# untitled.net
KiCad netlist of a schematic drawn in EAGLE
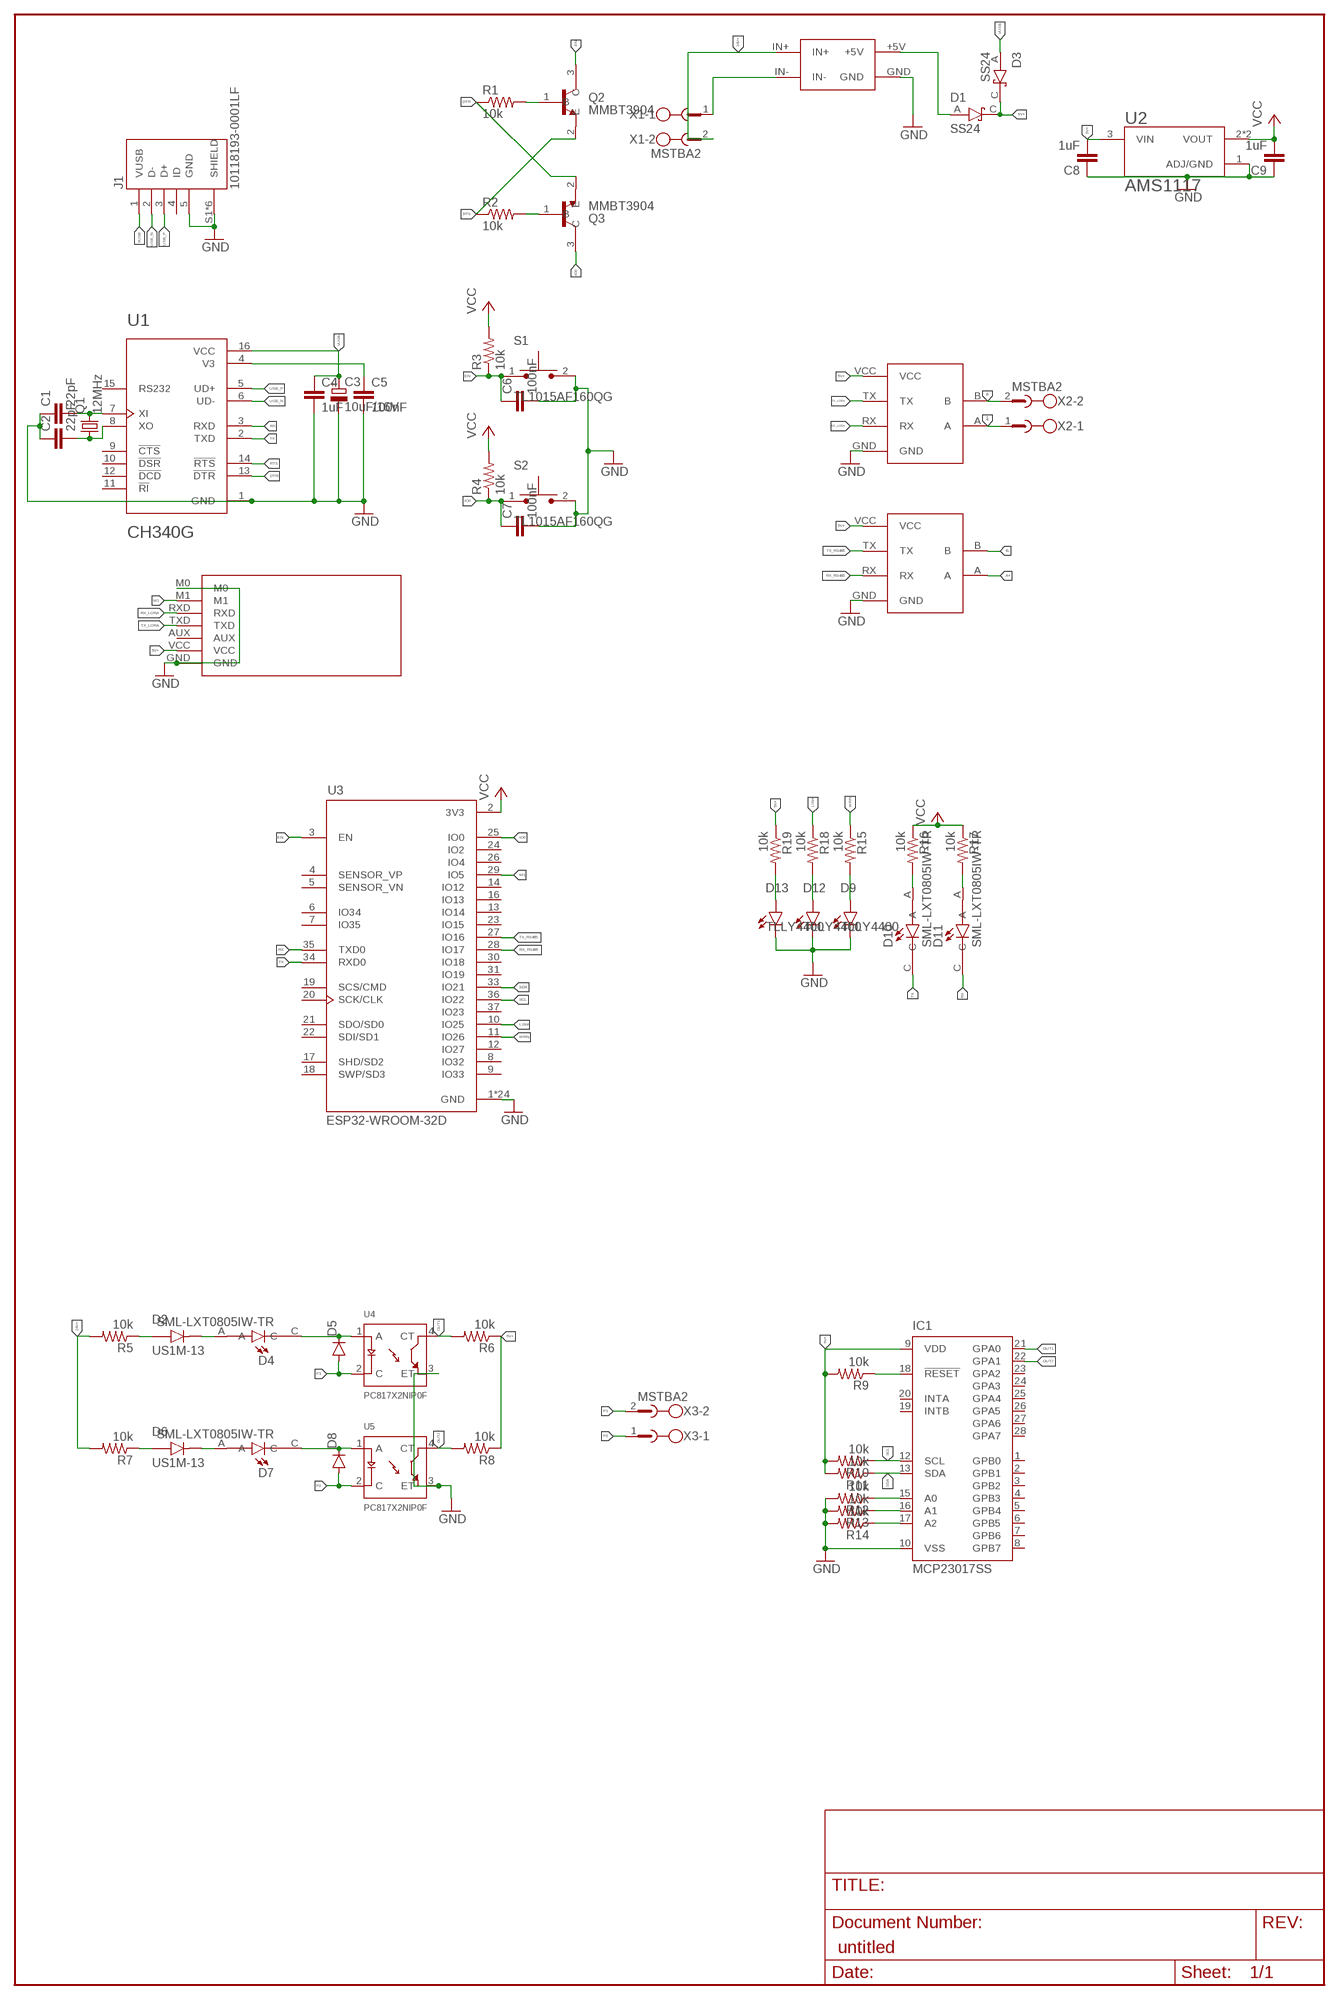
[diagram p0: schematic, sheet 1]

(export (version "E")
  (design (tool "Eeschema 10.0.6"))
  (components
    (comp (ref "C1")
      (value "22pF")
      (footprint "eagle-import:C0805K")
      (libsource (lib "eagle-import") (part "C-EUC0805K"))
    )
    (comp (ref "C2")
      (value "22pF")
      (footprint "eagle-import:C0805K")
      (libsource (lib "eagle-import") (part "C-EUC0805K"))
    )
    (comp (ref "C3")
      (value "10uF/16V")
      (footprint "eagle-import:153CLV-0505")
      (libsource (lib "eagle-import") (part "CPOL-EU153CLV-0505"))
    )
    (comp (ref "C4")
      (value "1uF")
      (footprint "eagle-import:C0805K")
      (libsource (lib "eagle-import") (part "C-EUC0805K"))
    )
    (comp (ref "C5")
      (value "100nF")
      (footprint "eagle-import:C0805K")
      (libsource (lib "eagle-import") (part "C-EUC0805K"))
    )
    (comp (ref "C6")
      (value "100nF")
      (footprint "eagle-import:C0805K")
      (libsource (lib "eagle-import") (part "C-EUC0805K"))
    )
    (comp (ref "C7")
      (value "100nF")
      (footprint "eagle-import:C0805K")
      (libsource (lib "eagle-import") (part "C-EUC0805K"))
    )
    (comp (ref "C8")
      (value "1uF")
      (footprint "eagle-import:C0805K")
      (libsource (lib "eagle-import") (part "C-EUC0805K"))
    )
    (comp (ref "C9")
      (value "1uF")
      (footprint "eagle-import:C0805K")
      (libsource (lib "eagle-import") (part "C-EUC0805K"))
    )
    (comp (ref "D1")
      (value "SS24")
      (footprint "eagle-import:DIOM5336X265N")
      (fields (field (name "MF") "ON Semiconductor"))
      (libsource (lib "eagle-import") (part "SS24"))
    )
    (comp (ref "D2")
      (value "US1M-13")
      (footprint "eagle-import:DIOM5226X240N")
      (fields (field (name "MF") "Diodes Incorporated"))
      (libsource (lib "eagle-import") (part "US1M-13"))
    )
    (comp (ref "D3")
      (value "SS24")
      (footprint "eagle-import:DIOM5336X265N")
      (fields (field (name "MF") "ON Semiconductor"))
      (libsource (lib "eagle-import") (part "SS24"))
    )
    (comp (ref "D4")
      (value "SML-LXT0805IW-TR")
      (footprint "eagle-import:LEDC2012X120N")
      (fields (field (name "MF") "Lumex Opto/Components"))
      (libsource (lib "eagle-import") (part "SML-LXT0805IW-TR"))
    )
    (comp (ref "D5")
      (value "DIODE-SOD123")
      (footprint "eagle-import:SOD123")
      (libsource (lib "eagle-import") (part "DIODE-SOD123"))
    )
    (comp (ref "D6")
      (value "US1M-13")
      (footprint "eagle-import:DIOM5226X240N")
      (fields (field (name "MF") "Diodes Incorporated"))
      (libsource (lib "eagle-import") (part "US1M-13"))
    )
    (comp (ref "D7")
      (value "SML-LXT0805IW-TR")
      (footprint "eagle-import:LEDC2012X120N")
      (fields (field (name "MF") "Lumex Opto/Components"))
      (libsource (lib "eagle-import") (part "SML-LXT0805IW-TR"))
    )
    (comp (ref "D8")
      (value "DIODE-SOD123")
      (footprint "eagle-import:SOD123")
      (libsource (lib "eagle-import") (part "DIODE-SOD123"))
    )
    (comp (ref "D9")
      (value "TLLY4400")
      (footprint "eagle-import:LED3MM")
      (fields (field (name "MF") "VISHAY SEMICONDUCTOR"))
      (libsource (lib "eagle-import") (part "TLLY4400"))
    )
    (comp (ref "D10")
      (value "SML-LXT0805IW-TR")
      (footprint "eagle-import:LEDC2012X120N")
      (fields (field (name "MF") "Lumex Opto/Components"))
      (libsource (lib "eagle-import") (part "SML-LXT0805IW-TR"))
    )
    (comp (ref "D11")
      (value "SML-LXT0805IW-TR")
      (footprint "eagle-import:LEDC2012X120N")
      (fields (field (name "MF") "Lumex Opto/Components"))
      (libsource (lib "eagle-import") (part "SML-LXT0805IW-TR"))
    )
    (comp (ref "D12")
      (value "TLLY4400")
      (footprint "eagle-import:LED3MM")
      (fields (field (name "MF") "VISHAY SEMICONDUCTOR"))
      (libsource (lib "eagle-import") (part "TLLY4400"))
    )
    (comp (ref "D13")
      (value "TLLY4400")
      (footprint "eagle-import:LED3MM")
      (fields (field (name "MF") "VISHAY SEMICONDUCTOR"))
      (libsource (lib "eagle-import") (part "TLLY4400"))
    )
    (comp (ref "EBYTEE220-900T22D1")
      (value "EBYTEE220-900T22D")
      (footprint "eagle-import:EBYTEE220-900T22D")
      (libsource (lib "eagle-import") (part "EBYTEE220-900T22D"))
    )
    (comp (ref "IC1")
      (value "MCP23017SS")
      (footprint "eagle-import:SSOP28")
      (fields (field (name "MF") "MICROCHIP") (field (name "MPN") "MCP23017-E/SS"))
      (libsource (lib "eagle-import") (part "MCP23017SS"))
    )
    (comp (ref "J1")
      (value "10118193-0001LF")
      (footprint "eagle-import:FCI_10118193-0001LF")
      (fields (field (name "MF") "FCI"))
      (libsource (lib "eagle-import") (part "10118193-0001LF"))
    )
    (comp (ref "Q1")
      (value "12MHz")
      (footprint "eagle-import:SM49")
      (libsource (lib "eagle-import") (part "CRYSTALSM49"))
    )
    (comp (ref "Q2")
      (value "MMBT3904")
      (footprint "eagle-import:SOT95P240X120-3N")
      (fields (field (name "MF") "ON Semiconductor"))
      (libsource (lib "eagle-import") (part "MMBT3904"))
    )
    (comp (ref "Q3")
      (value "MMBT3904")
      (footprint "eagle-import:SOT95P240X120-3N")
      (fields (field (name "MF") "ON Semiconductor"))
      (libsource (lib "eagle-import") (part "MMBT3904"))
    )
    (comp (ref "R1")
      (value "10k")
      (footprint "eagle-import:M0805")
      (libsource (lib "eagle-import") (part "rcl_334_R-US_M0805"))
    )
    (comp (ref "R2")
      (value "10k")
      (footprint "eagle-import:M0805")
      (libsource (lib "eagle-import") (part "rcl_334_R-US_M0805"))
    )
    (comp (ref "R3")
      (value "10k")
      (footprint "eagle-import:M0805")
      (libsource (lib "eagle-import") (part "rcl_334_R-US_M0805"))
    )
    (comp (ref "R4")
      (value "10k")
      (footprint "eagle-import:M0805")
      (libsource (lib "eagle-import") (part "rcl_334_R-US_M0805"))
    )
    (comp (ref "R5")
      (value "10k")
      (footprint "eagle-import:0207_12")
      (libsource (lib "eagle-import") (part "R-US_0207/12"))
    )
    (comp (ref "R6")
      (value "10k")
      (footprint "eagle-import:M0805")
      (libsource (lib "eagle-import") (part "rcl_334_R-US_M0805"))
    )
    (comp (ref "R7")
      (value "10k")
      (footprint "eagle-import:0207_12")
      (libsource (lib "eagle-import") (part "R-US_0207/12"))
    )
    (comp (ref "R8")
      (value "10k")
      (footprint "eagle-import:M0805")
      (libsource (lib "eagle-import") (part "rcl_334_R-US_M0805"))
    )
    (comp (ref "R9")
      (value "10k")
      (footprint "eagle-import:M0805")
      (libsource (lib "eagle-import") (part "rcl_334_R-US_M0805"))
    )
    (comp (ref "R10")
      (value "10k")
      (footprint "eagle-import:M0805")
      (libsource (lib "eagle-import") (part "rcl_334_R-US_M0805"))
    )
    (comp (ref "R11")
      (value "10k")
      (footprint "eagle-import:M0805")
      (libsource (lib "eagle-import") (part "rcl_334_R-US_M0805"))
    )
    (comp (ref "R12")
      (value "10k")
      (footprint "eagle-import:M0805")
      (libsource (lib "eagle-import") (part "rcl_334_R-US_M0805"))
    )
    (comp (ref "R13")
      (value "10k")
      (footprint "eagle-import:M0805")
      (libsource (lib "eagle-import") (part "rcl_334_R-US_M0805"))
    )
    (comp (ref "R14")
      (value "10k")
      (footprint "eagle-import:M0805")
      (libsource (lib "eagle-import") (part "rcl_334_R-US_M0805"))
    )
    (comp (ref "R15")
      (value "10k")
      (footprint "eagle-import:M0805")
      (libsource (lib "eagle-import") (part "rcl_334_R-US_M0805"))
    )
    (comp (ref "R16")
      (value "10k")
      (footprint "eagle-import:M0805")
      (libsource (lib "eagle-import") (part "rcl_334_R-US_M0805"))
    )
    (comp (ref "R17")
      (value "10k")
      (footprint "eagle-import:M0805")
      (libsource (lib "eagle-import") (part "rcl_334_R-US_M0805"))
    )
    (comp (ref "R18")
      (value "10k")
      (footprint "eagle-import:M0805")
      (libsource (lib "eagle-import") (part "rcl_334_R-US_M0805"))
    )
    (comp (ref "R19")
      (value "10k")
      (footprint "eagle-import:M0805")
      (libsource (lib "eagle-import") (part "rcl_334_R-US_M0805"))
    )
    (comp (ref "S1")
      (value "TL1015AF160QG")
      (footprint "eagle-import:SW_TL1015AF160QG")
      (fields (field (name "MF") "E-Switch"))
      (libsource (lib "eagle-import") (part "TL1015AF160QG"))
    )
    (comp (ref "S2")
      (value "TL1015AF160QG")
      (footprint "eagle-import:SW_TL1015AF160QG")
      (fields (field (name "MF") "E-Switch"))
      (libsource (lib "eagle-import") (part "TL1015AF160QG"))
    )
    (comp (ref "SUPER-STEPDOWN1")
      (value "SUPER-STEPDOWN")
      (footprint "eagle-import:SUPER-STEPDOWN")
      (libsource (lib "eagle-import") (part "SUPER-STEPDOWN"))
    )
    (comp (ref "TTL-RS1")
      (value "TTL-RS485")
      (footprint "eagle-import:TTL-RS485")
      (libsource (lib "eagle-import") (part "TTL-RS485"))
    )
    (comp (ref "TTL-RS2")
      (value "TTL-RS485")
      (footprint "eagle-import:TTL-RS485")
      (libsource (lib "eagle-import") (part "TTL-RS485"))
    )
    (comp (ref "U1")
      (value "CH340G")
      (footprint "eagle-import:SOIC127P600X180-16N")
      (fields (field (name "MF") "WCH") (field (name "MP") "Ch340G"))
      (libsource (lib "eagle-import") (part "CH340G"))
    )
    (comp (ref "U2")
      (value "AMS1117")
      (footprint "eagle-import:SOT229P700X180-4N")
      (fields (field (name "MF") "Advanced Monolithic Systems"))
      (libsource (lib "eagle-import") (part "AMS1117"))
    )
    (comp (ref "U3")
      (value "ESP32-WROOM-32D")
      (footprint "eagle-import:MODULE_ESP32-WROOM-32D")
      (fields (field (name "MF") "Espressif Systems"))
      (libsource (lib "eagle-import") (part "ESP32-WROOM-32D"))
    )
    (comp (ref "U4")
      (value "PC817X2NIP0F")
      (footprint "eagle-import:SOT254P975X400-4N")
      (fields (field (name "MF") "Sharp Microelectronics"))
      (libsource (lib "eagle-import") (part "PC817X2NIP0F"))
    )
    (comp (ref "U5")
      (value "PC817X2NIP0F")
      (footprint "eagle-import:SOT254P975X400-4N")
      (fields (field (name "MF") "Sharp Microelectronics"))
      (libsource (lib "eagle-import") (part "PC817X2NIP0F"))
    )
    (comp (ref "X1")
      (value "MSTBA2")
      (footprint "eagle-import:MSTBA2")
      (fields (field (name "MF") "FARNELL") (field (name "MPN") "1757242"))
      (libsource (lib "eagle-import") (part "MSTBA2"))
    )
    (comp (ref "X2")
      (value "MSTBA2")
      (footprint "eagle-import:MSTBA2")
      (fields (field (name "MF") "FARNELL") (field (name "MPN") "1757242"))
      (libsource (lib "eagle-import") (part "MSTBA2"))
    )
    (comp (ref "X3")
      (value "MSTBA2")
      (footprint "eagle-import:MSTBA2")
      (fields (field (name "MF") "FARNELL") (field (name "MPN") "1757242"))
      (libsource (lib "eagle-import") (part "MSTBA2"))
    )
  )
  (nets
    (net (code "1") (name "5V+") (class "Default")
      (node (ref "C8") (pin "2") (pinfunction "2_2") (pintype "passive"))
      (node (ref "D1") (pin "C") (pinfunction "K_C") (pintype "passive"))
      (node (ref "D3") (pin "C") (pinfunction "K_C") (pintype "passive"))
      (node (ref "EBYTEE220-900T22D1") (pin "VCC") (pinfunction "VCC_VCC") (pintype "bidirectional"))
      (node (ref "IC1") (pin "9") (pinfunction "VDD_9") (pintype "power_in"))
      (node (ref "R10") (pin "2") (pinfunction "2_2") (pintype "passive"))
      (node (ref "R11") (pin "2") (pinfunction "2_2") (pintype "passive"))
      (node (ref "R19") (pin "1") (pinfunction "1_1") (pintype "passive"))
      (node (ref "R6") (pin "1") (pinfunction "1_1") (pintype "passive"))
      (node (ref "R8") (pin "1") (pinfunction "1_1") (pintype "passive"))
      (node (ref "R9") (pin "2") (pinfunction "2_2") (pintype "passive"))
      (node (ref "TTL-RS1") (pin "VCC") (pinfunction "VCC_VCC") (pintype "bidirectional"))
      (node (ref "TTL-RS2") (pin "VCC") (pinfunction "VCC_VCC") (pintype "bidirectional"))
      (node (ref "U2") (pin "3") (pinfunction "VIN_3") (pintype "input"))
    )
    (net (code "2") (name "24V+") (class "Default")
      (node (ref "R5") (pin "2") (pinfunction "2_2") (pintype "passive"))
      (node (ref "R7") (pin "2") (pinfunction "2_2") (pintype "passive"))
      (node (ref "SUPER-STEPDOWN1") (pin "IN+") (pinfunction "IN+_IN+") (pintype "bidirectional"))
      (node (ref "X1") (pin "2") (pinfunction "1_2") (pintype "passive"))
    )
    (net (code "3") (name "A+") (class "Default")
      (node (ref "TTL-RS1") (pin "A") (pinfunction "A_A") (pintype "bidirectional"))
      (node (ref "TTL-RS2") (pin "A") (pinfunction "A_A") (pintype "bidirectional"))
      (node (ref "X2") (pin "1") (pinfunction "1_1") (pintype "passive"))
    )
    (net (code "4") (name "B-") (class "Default")
      (node (ref "TTL-RS1") (pin "B") (pinfunction "B_B") (pintype "bidirectional"))
      (node (ref "TTL-RS2") (pin "B") (pinfunction "B_B") (pintype "bidirectional"))
      (node (ref "X2") (pin "2") (pinfunction "1_2") (pintype "passive"))
    )
    (net (code "5") (name "DTR") (class "Default")
      (node (ref "Q3") (pin "2") (pinfunction "E_2") (pintype "passive"))
      (node (ref "R1") (pin "1") (pinfunction "1_1") (pintype "passive"))
      (node (ref "U1") (pin "13") (pinfunction "~{DTR}_13") (pintype "output"))
    )
    (net (code "6") (name "EN") (class "Default")
      (node (ref "C6") (pin "1") (pinfunction "1_1") (pintype "passive"))
      (node (ref "Q2") (pin "3") (pinfunction "C_3") (pintype "passive"))
      (node (ref "R3") (pin "1") (pinfunction "1_1") (pintype "passive"))
      (node (ref "S1") (pin "1") (pinfunction "1_1") (pintype "passive"))
      (node (ref "U3") (pin "3") (pinfunction "EN_3") (pintype "input"))
    )
    (net (code "7") (name "GND") (class "Default")
      (node (ref "C1") (pin "1") (pinfunction "1_1") (pintype "passive"))
      (node (ref "C2") (pin "1") (pinfunction "1_1") (pintype "passive"))
      (node (ref "C3") (pin "-") (pinfunction "-_-") (pintype "passive"))
      (node (ref "C4") (pin "2") (pinfunction "2_2") (pintype "passive"))
      (node (ref "C5") (pin "2") (pinfunction "2_2") (pintype "passive"))
      (node (ref "C6") (pin "2") (pinfunction "2_2") (pintype "passive"))
      (node (ref "C7") (pin "2") (pinfunction "2_2") (pintype "passive"))
      (node (ref "C8") (pin "1") (pinfunction "1_1") (pintype "passive"))
      (node (ref "C9") (pin "1") (pinfunction "1_1") (pintype "passive"))
      (node (ref "D12") (pin "K") (pinfunction "C_K") (pintype "passive"))
      (node (ref "D13") (pin "K") (pinfunction "C_K") (pintype "passive"))
      (node (ref "D9") (pin "K") (pinfunction "C_K") (pintype "passive"))
      (node (ref "EBYTEE220-900T22D1") (pin "GND") (pinfunction "GND_GND") (pintype "bidirectional"))
      (node (ref "EBYTEE220-900T22D1") (pin "M0") (pinfunction "M0_M0") (pintype "bidirectional"))
      (node (ref "IC1") (pin "10") (pinfunction "VSS_10") (pintype "power_in"))
      (node (ref "J1") (pin "5") (pinfunction "GND_5") (pintype "passive"))
      (node (ref "J1") (pin "S1") (pinfunction "SHIELD_S1") (pintype "passive"))
      (node (ref "J1") (pin "S2") (pinfunction "SHIELD_S2") (pintype "passive"))
      (node (ref "J1") (pin "S3") (pinfunction "SHIELD_S3") (pintype "passive"))
      (node (ref "J1") (pin "S4") (pinfunction "SHIELD_S4") (pintype "passive"))
      (node (ref "J1") (pin "S5") (pinfunction "SHIELD_S5") (pintype "passive"))
      (node (ref "J1") (pin "S6") (pinfunction "SHIELD_S6") (pintype "passive"))
      (node (ref "R12") (pin "2") (pinfunction "2_2") (pintype "passive"))
      (node (ref "R13") (pin "2") (pinfunction "2_2") (pintype "passive"))
      (node (ref "R14") (pin "2") (pinfunction "2_2") (pintype "passive"))
      (node (ref "S1") (pin "2") (pinfunction "2_2") (pintype "passive"))
      (node (ref "S2") (pin "2") (pinfunction "2_2") (pintype "passive"))
      (node (ref "SUPER-STEPDOWN1") (pin "GND") (pinfunction "GND_GND") (pintype "bidirectional"))
      (node (ref "TTL-RS1") (pin "GND") (pinfunction "GND_GND") (pintype "bidirectional"))
      (node (ref "TTL-RS2") (pin "GND") (pinfunction "GND_GND") (pintype "bidirectional"))
      (node (ref "U1") (pin "1") (pinfunction "GND_1") (pintype "power_in"))
      (node (ref "U2") (pin "1") (pinfunction "ADJ/GND_1") (pintype "power_in"))
      (node (ref "U3") (pin "1") (pinfunction "GND_1") (pintype "power_in"))
      (node (ref "U3") (pin "15") (pinfunction "GND_15") (pintype "power_in"))
      (node (ref "U3") (pin "38") (pinfunction "GND_38") (pintype "power_in"))
      (node (ref "U3") (pin "39_1") (pinfunction "GND_39_1") (pintype "power_in"))
      (node (ref "U3") (pin "39_10") (pinfunction "GND_39_10") (pintype "power_in"))
      (node (ref "U3") (pin "39_11") (pinfunction "GND_39_11") (pintype "power_in"))
      (node (ref "U3") (pin "39_12") (pinfunction "GND_39_12") (pintype "power_in"))
      (node (ref "U3") (pin "39_13") (pinfunction "GND_39_13") (pintype "power_in"))
      (node (ref "U3") (pin "39_14") (pinfunction "GND_39_14") (pintype "power_in"))
      (node (ref "U3") (pin "39_15") (pinfunction "GND_39_15") (pintype "power_in"))
      (node (ref "U3") (pin "39_16") (pinfunction "GND_39_16") (pintype "power_in"))
      (node (ref "U3") (pin "39_17") (pinfunction "GND_39_17") (pintype "power_in"))
      (node (ref "U3") (pin "39_18") (pinfunction "GND_39_18") (pintype "power_in"))
      (node (ref "U3") (pin "39_19") (pinfunction "GND_39_19") (pintype "power_in"))
      (node (ref "U3") (pin "39_2") (pinfunction "GND_39_2") (pintype "power_in"))
      (node (ref "U3") (pin "39_20") (pinfunction "GND_39_20") (pintype "power_in"))
      (node (ref "U3") (pin "39_21") (pinfunction "GND_39_21") (pintype "power_in"))
      (node (ref "U3") (pin "39_3") (pinfunction "GND_39_3") (pintype "power_in"))
      (node (ref "U3") (pin "39_4") (pinfunction "GND_39_4") (pintype "power_in"))
      (node (ref "U3") (pin "39_5") (pinfunction "GND_39_5") (pintype "power_in"))
      (node (ref "U3") (pin "39_6") (pinfunction "GND_39_6") (pintype "power_in"))
      (node (ref "U3") (pin "39_7") (pinfunction "GND_39_7") (pintype "power_in"))
      (node (ref "U3") (pin "39_8") (pinfunction "GND_39_8") (pintype "power_in"))
      (node (ref "U3") (pin "39_9") (pinfunction "GND_39_9") (pintype "power_in"))
      (node (ref "U4") (pin "3") (pinfunction "ET_3") (pintype "passive"))
      (node (ref "U5") (pin "3") (pinfunction "ET_3") (pintype "passive"))
    )
    (net (code "8") (name "IO0") (class "Default")
      (node (ref "C7") (pin "1") (pinfunction "1_1") (pintype "passive"))
      (node (ref "Q3") (pin "3") (pinfunction "C_3") (pintype "passive"))
      (node (ref "R4") (pin "1") (pinfunction "1_1") (pintype "passive"))
      (node (ref "S2") (pin "1") (pinfunction "1_1") (pintype "passive"))
      (node (ref "U3") (pin "25") (pinfunction "IO0_25") (pintype "bidirectional"))
    )
    (net (code "9") (name "LINK") (class "Default")
      (node (ref "R18") (pin "1") (pinfunction "1_1") (pintype "passive"))
      (node (ref "U3") (pin "10") (pinfunction "IO25_10") (pintype "bidirectional"))
    )
    (net (code "10") (name "M1") (class "Default")
      (node (ref "EBYTEE220-900T22D1") (pin "M1") (pinfunction "M1_M1") (pintype "bidirectional"))
      (node (ref "U3") (pin "29") (pinfunction "IO5_29") (pintype "bidirectional"))
    )
    (net (code "11") (name "Net-(D1-PadA)") (class "Default")
      (node (ref "D1") (pin "A") (pinfunction "A_A") (pintype "passive"))
      (node (ref "SUPER-STEPDOWN1") (pin "+5V") (pinfunction "+5V_+5V") (pintype "bidirectional"))
    )
    (net (code "12") (name "Net-(D2-K)") (class "Default")
      (node (ref "D2") (pin "C") (pinfunction "K_C") (pintype "passive"))
      (node (ref "D4") (pin "A") (pinfunction "A_A") (pintype "passive"))
    )
    (net (code "13") (name "Net-(D2-PadA)") (class "Default")
      (node (ref "D2") (pin "A") (pinfunction "A_A") (pintype "passive"))
      (node (ref "R5") (pin "1") (pinfunction "1_1") (pintype "passive"))
    )
    (net (code "14") (name "Net-(D6-K)") (class "Default")
      (node (ref "D6") (pin "C") (pinfunction "K_C") (pintype "passive"))
      (node (ref "D7") (pin "A") (pinfunction "A_A") (pintype "passive"))
    )
    (net (code "15") (name "Net-(D6-PadA)") (class "Default")
      (node (ref "D6") (pin "A") (pinfunction "A_A") (pintype "passive"))
      (node (ref "R7") (pin "1") (pinfunction "1_1") (pintype "passive"))
    )
    (net (code "16") (name "Net-(D9-PadA)") (class "Default")
      (node (ref "D9") (pin "A") (pinfunction "A_A") (pintype "passive"))
      (node (ref "R15") (pin "2") (pinfunction "2_2") (pintype "passive"))
    )
    (net (code "17") (name "Net-(D10-PadA)") (class "Default")
      (node (ref "D10") (pin "A") (pinfunction "A_A") (pintype "passive"))
      (node (ref "R16") (pin "2") (pinfunction "2_2") (pintype "passive"))
    )
    (net (code "18") (name "Net-(D11-PadA)") (class "Default")
      (node (ref "D11") (pin "A") (pinfunction "A_A") (pintype "passive"))
      (node (ref "R17") (pin "2") (pinfunction "2_2") (pintype "passive"))
    )
    (net (code "19") (name "Net-(D12-PadA)") (class "Default")
      (node (ref "D12") (pin "A") (pinfunction "A_A") (pintype "passive"))
      (node (ref "R18") (pin "2") (pinfunction "2_2") (pintype "passive"))
    )
    (net (code "20") (name "Net-(D13-PadA)") (class "Default")
      (node (ref "D13") (pin "A") (pinfunction "A_A") (pintype "passive"))
      (node (ref "R19") (pin "2") (pinfunction "2_2") (pintype "passive"))
    )
    (net (code "21") (name "Net-(IC1-A0)") (class "Default")
      (node (ref "IC1") (pin "15") (pinfunction "A0_15") (pintype "input"))
      (node (ref "R12") (pin "1") (pinfunction "1_1") (pintype "passive"))
    )
    (net (code "22") (name "Net-(IC1-A1)") (class "Default")
      (node (ref "IC1") (pin "16") (pinfunction "A1_16") (pintype "input"))
      (node (ref "R13") (pin "1") (pinfunction "1_1") (pintype "passive"))
    )
    (net (code "23") (name "Net-(IC1-A2)") (class "Default")
      (node (ref "IC1") (pin "17") (pinfunction "A2_17") (pintype "input"))
      (node (ref "R14") (pin "1") (pinfunction "1_1") (pintype "passive"))
    )
    (net (code "24") (name "Net-(IC1-~{RESET})") (class "Default")
      (node (ref "IC1") (pin "18") (pinfunction "~{RESET}_18") (pintype "input"))
      (node (ref "R9") (pin "1") (pinfunction "1_1") (pintype "passive"))
    )
    (net (code "25") (name "Net-(Q2-B)") (class "Default")
      (node (ref "Q2") (pin "1") (pinfunction "B_1") (pintype "passive"))
      (node (ref "R1") (pin "2") (pinfunction "2_2") (pintype "passive"))
    )
    (net (code "26") (name "Net-(Q3-B)") (class "Default")
      (node (ref "Q3") (pin "1") (pinfunction "B_1") (pintype "passive"))
      (node (ref "R2") (pin "2") (pinfunction "2_2") (pintype "passive"))
    )
    (net (code "27") (name "Net-(SUPER-STEPDOWN1-PadIN-)") (class "Default")
      (node (ref "SUPER-STEPDOWN1") (pin "IN-") (pinfunction "IN-_IN-") (pintype "bidirectional"))
      (node (ref "X1") (pin "1") (pinfunction "1_1") (pintype "passive"))
    )
    (net (code "28") (name "Net-(U1-V3)") (class "Default")
      (node (ref "C5") (pin "1") (pinfunction "1_1") (pintype "passive"))
      (node (ref "U1") (pin "4") (pinfunction "V3_4") (pintype "power_in"))
    )
    (net (code "29") (name "Net-(U1-XI)") (class "Default")
      (node (ref "C1") (pin "2") (pinfunction "2_2") (pintype "passive"))
      (node (ref "Q1") (pin "2") (pinfunction "2_2") (pintype "passive"))
      (node (ref "U1") (pin "7") (pinfunction "XI_7") (pintype "input"))
    )
    (net (code "30") (name "Net-(U1-XO)") (class "Default")
      (node (ref "C2") (pin "2") (pinfunction "2_2") (pintype "passive"))
      (node (ref "Q1") (pin "1") (pinfunction "1_1") (pintype "passive"))
      (node (ref "U1") (pin "8") (pinfunction "XO_8") (pintype "output"))
    )
    (net (code "31") (name "Net-(U4-A)") (class "Default")
      (node (ref "D4") (pin "C") (pinfunction "C_C") (pintype "passive"))
      (node (ref "D5") (pin "C") (pinfunction "C_C") (pintype "passive"))
      (node (ref "U4") (pin "1") (pinfunction "A_1") (pintype "passive"))
    )
    (net (code "32") (name "Net-(U5-A)") (class "Default")
      (node (ref "D7") (pin "C") (pinfunction "C_C") (pintype "passive"))
      (node (ref "D8") (pin "C") (pinfunction "C_C") (pintype "passive"))
      (node (ref "U5") (pin "1") (pinfunction "A_1") (pintype "passive"))
    )
    (net (code "33") (name "OUT1") (class "Default")
      (node (ref "IC1") (pin "21") (pinfunction "GPA0_21") (pintype "bidirectional"))
      (node (ref "R6") (pin "2") (pinfunction "2_2") (pintype "passive"))
      (node (ref "U4") (pin "4") (pinfunction "CT_4") (pintype "passive"))
    )
    (net (code "34") (name "OUT2") (class "Default")
      (node (ref "IC1") (pin "22") (pinfunction "GPA1_22") (pintype "bidirectional"))
      (node (ref "R8") (pin "2") (pinfunction "2_2") (pintype "passive"))
      (node (ref "U5") (pin "4") (pinfunction "CT_4") (pintype "passive"))
    )
    (net (code "35") (name "P1") (class "Default")
      (node (ref "D5") (pin "A") (pinfunction "A_A") (pintype "passive"))
      (node (ref "U4") (pin "2") (pinfunction "C_2") (pintype "passive"))
      (node (ref "X3") (pin "2") (pinfunction "1_2") (pintype "passive"))
    )
    (net (code "36") (name "P2") (class "Default")
      (node (ref "D8") (pin "A") (pinfunction "A_A") (pintype "passive"))
      (node (ref "U5") (pin "2") (pinfunction "C_2") (pintype "passive"))
      (node (ref "X3") (pin "1") (pinfunction "1_1") (pintype "passive"))
    )
    (net (code "37") (name "RTS") (class "Default")
      (node (ref "Q2") (pin "2") (pinfunction "E_2") (pintype "passive"))
      (node (ref "R2") (pin "1") (pinfunction "1_1") (pintype "passive"))
      (node (ref "U1") (pin "14") (pinfunction "~{RTS}_14") (pintype "output"))
    )
    (net (code "38") (name "RX") (class "Default")
      (node (ref "D11") (pin "C") (pinfunction "C_C") (pintype "passive"))
      (node (ref "U1") (pin "3") (pinfunction "RXD_3") (pintype "input"))
      (node (ref "U3") (pin "35") (pinfunction "TXD0_35") (pintype "bidirectional"))
    )
    (net (code "39") (name "RX_LORA") (class "Default")
      (node (ref "EBYTEE220-900T22D1") (pin "RXD") (pinfunction "RXD_RXD") (pintype "bidirectional"))
      (node (ref "TTL-RS1") (pin "RX") (pinfunction "RX_RX") (pintype "bidirectional"))
    )
    (net (code "40") (name "RX_RS485") (class "Default")
      (node (ref "TTL-RS2") (pin "RX") (pinfunction "RX_RX") (pintype "bidirectional"))
      (node (ref "U3") (pin "28") (pinfunction "IO17_28") (pintype "bidirectional"))
    )
    (net (code "41") (name "SCL") (class "Default")
      (node (ref "IC1") (pin "12") (pinfunction "SCL_12") (pintype "input"))
      (node (ref "R10") (pin "1") (pinfunction "1_1") (pintype "passive"))
      (node (ref "U3") (pin "36") (pinfunction "IO22_36") (pintype "bidirectional"))
    )
    (net (code "42") (name "SDA") (class "Default")
      (node (ref "IC1") (pin "13") (pinfunction "SDA_13") (pintype "bidirectional"))
      (node (ref "R11") (pin "1") (pinfunction "1_1") (pintype "passive"))
      (node (ref "U3") (pin "33") (pinfunction "IO21_33") (pintype "bidirectional"))
    )
    (net (code "43") (name "TX") (class "Default")
      (node (ref "D10") (pin "C") (pinfunction "C_C") (pintype "passive"))
      (node (ref "U1") (pin "2") (pinfunction "TXD_2") (pintype "output"))
      (node (ref "U3") (pin "34") (pinfunction "RXD0_34") (pintype "bidirectional"))
    )
    (net (code "44") (name "TX_LORA") (class "Default")
      (node (ref "EBYTEE220-900T22D1") (pin "TXD") (pinfunction "TXD_TXD") (pintype "bidirectional"))
      (node (ref "TTL-RS1") (pin "TX") (pinfunction "TX_TX") (pintype "bidirectional"))
    )
    (net (code "45") (name "TX_RS485") (class "Default")
      (node (ref "TTL-RS2") (pin "TX") (pinfunction "TX_TX") (pintype "bidirectional"))
      (node (ref "U3") (pin "27") (pinfunction "IO16_27") (pintype "bidirectional"))
    )
    (net (code "46") (name "USB_N") (class "Default")
      (node (ref "J1") (pin "2") (pinfunction "D-_2") (pintype "passive"))
      (node (ref "U1") (pin "6") (pinfunction "UD-_6") (pintype "bidirectional"))
    )
    (net (code "47") (name "USB_P") (class "Default")
      (node (ref "J1") (pin "3") (pinfunction "D+_3") (pintype "passive"))
      (node (ref "U1") (pin "5") (pinfunction "UD+_5") (pintype "bidirectional"))
    )
    (net (code "48") (name "VCC") (class "Default")
      (node (ref "C9") (pin "2") (pinfunction "2_2") (pintype "passive"))
      (node (ref "R16") (pin "1") (pinfunction "1_1") (pintype "passive"))
      (node (ref "R17") (pin "1") (pinfunction "1_1") (pintype "passive"))
      (node (ref "R3") (pin "2") (pinfunction "2_2") (pintype "passive"))
      (node (ref "R4") (pin "2") (pinfunction "2_2") (pintype "passive"))
      (node (ref "U2") (pin "2") (pinfunction "VOUT_2") (pintype "output"))
      (node (ref "U2") (pin "4") (pinfunction "VOUT_4") (pintype "output"))
      (node (ref "U3") (pin "2") (pinfunction "3V3_2") (pintype "power_in"))
    )
    (net (code "49") (name "VUSB") (class "Default")
      (node (ref "C3") (pin "+") (pinfunction "+_+") (pintype "passive"))
      (node (ref "C4") (pin "1") (pinfunction "1_1") (pintype "passive"))
      (node (ref "D3") (pin "A") (pinfunction "A_A") (pintype "passive"))
      (node (ref "J1") (pin "1") (pinfunction "VUSB_1") (pintype "passive"))
      (node (ref "U1") (pin "16") (pinfunction "VCC_16") (pintype "power_in"))
    )
    (net (code "50") (name "WRN") (class "Default")
      (node (ref "R15") (pin "1") (pinfunction "1_1") (pintype "passive"))
      (node (ref "U3") (pin "11") (pinfunction "IO26_11") (pintype "bidirectional"))
    )
    (net (code "51") (name "unconnected-(EBYTEE220-900T22D1-PadAUX)") (class "Default")
      (node (ref "EBYTEE220-900T22D1") (pin "AUX") (pinfunction "AUX_AUX") (pintype "bidirectional"))
    )
    (net (code "52") (name "unconnected-(IC1-GPA2-Pad23)") (class "Default")
      (node (ref "IC1") (pin "23") (pinfunction "GPA2_23") (pintype "bidirectional"))
    )
    (net (code "53") (name "unconnected-(IC1-GPA3-Pad24)") (class "Default")
      (node (ref "IC1") (pin "24") (pinfunction "GPA3_24") (pintype "bidirectional"))
    )
    (net (code "54") (name "unconnected-(IC1-GPA4-Pad25)") (class "Default")
      (node (ref "IC1") (pin "25") (pinfunction "GPA4_25") (pintype "bidirectional"))
    )
    (net (code "55") (name "unconnected-(IC1-GPA5-Pad26)") (class "Default")
      (node (ref "IC1") (pin "26") (pinfunction "GPA5_26") (pintype "bidirectional"))
    )
    (net (code "56") (name "unconnected-(IC1-GPA6-Pad27)") (class "Default")
      (node (ref "IC1") (pin "27") (pinfunction "GPA6_27") (pintype "bidirectional"))
    )
    (net (code "57") (name "unconnected-(IC1-GPA7-Pad28)") (class "Default")
      (node (ref "IC1") (pin "28") (pinfunction "GPA7_28") (pintype "bidirectional"))
    )
    (net (code "58") (name "unconnected-(IC1-GPB0-Pad1)") (class "Default")
      (node (ref "IC1") (pin "1") (pinfunction "GPB0_1") (pintype "bidirectional"))
    )
    (net (code "59") (name "unconnected-(IC1-GPB1-Pad2)") (class "Default")
      (node (ref "IC1") (pin "2") (pinfunction "GPB1_2") (pintype "bidirectional"))
    )
    (net (code "60") (name "unconnected-(IC1-GPB2-Pad3)") (class "Default")
      (node (ref "IC1") (pin "3") (pinfunction "GPB2_3") (pintype "bidirectional"))
    )
    (net (code "61") (name "unconnected-(IC1-GPB3-Pad4)") (class "Default")
      (node (ref "IC1") (pin "4") (pinfunction "GPB3_4") (pintype "bidirectional"))
    )
    (net (code "62") (name "unconnected-(IC1-GPB4-Pad5)") (class "Default")
      (node (ref "IC1") (pin "5") (pinfunction "GPB4_5") (pintype "bidirectional"))
    )
    (net (code "63") (name "unconnected-(IC1-GPB5-Pad6)") (class "Default")
      (node (ref "IC1") (pin "6") (pinfunction "GPB5_6") (pintype "bidirectional"))
    )
    (net (code "64") (name "unconnected-(IC1-GPB6-Pad7)") (class "Default")
      (node (ref "IC1") (pin "7") (pinfunction "GPB6_7") (pintype "bidirectional"))
    )
    (net (code "65") (name "unconnected-(IC1-GPB7-Pad8)") (class "Default")
      (node (ref "IC1") (pin "8") (pinfunction "GPB7_8") (pintype "bidirectional"))
    )
    (net (code "66") (name "unconnected-(IC1-INTA-Pad20)") (class "Default")
      (node (ref "IC1") (pin "20") (pinfunction "INTA_20") (pintype "output"))
    )
    (net (code "67") (name "unconnected-(IC1-INTB-Pad19)") (class "Default")
      (node (ref "IC1") (pin "19") (pinfunction "INTB_19") (pintype "output"))
    )
    (net (code "68") (name "unconnected-(J1-ID-Pad4)") (class "Default")
      (node (ref "J1") (pin "4") (pinfunction "ID_4") (pintype "passive"))
    )
    (net (code "69") (name "unconnected-(U1-RS232-Pad15)") (class "Default")
      (node (ref "U1") (pin "15") (pinfunction "RS232_15") (pintype "input"))
    )
    (net (code "70") (name "unconnected-(U1-~{CTS}-Pad9)") (class "Default")
      (node (ref "U1") (pin "9") (pinfunction "~{CTS}_9") (pintype "input"))
    )
    (net (code "71") (name "unconnected-(U1-~{DCD}-Pad12)") (class "Default")
      (node (ref "U1") (pin "12") (pinfunction "~{DCD}_12") (pintype "input"))
    )
    (net (code "72") (name "unconnected-(U1-~{DSR}-Pad10)") (class "Default")
      (node (ref "U1") (pin "10") (pinfunction "~{DSR}_10") (pintype "input"))
    )
    (net (code "73") (name "unconnected-(U1-~{RI}-Pad11)") (class "Default")
      (node (ref "U1") (pin "11") (pinfunction "~{RI}_11") (pintype "input"))
    )
    (net (code "74") (name "unconnected-(U3-IO2-Pad24)") (class "Default")
      (node (ref "U3") (pin "24") (pinfunction "IO2_24") (pintype "bidirectional"))
    )
    (net (code "75") (name "unconnected-(U3-IO4-Pad26)") (class "Default")
      (node (ref "U3") (pin "26") (pinfunction "IO4_26") (pintype "bidirectional"))
    )
    (net (code "76") (name "unconnected-(U3-IO12-Pad14)") (class "Default")
      (node (ref "U3") (pin "14") (pinfunction "IO12_14") (pintype "bidirectional"))
    )
    (net (code "77") (name "unconnected-(U3-IO13-Pad16)") (class "Default")
      (node (ref "U3") (pin "16") (pinfunction "IO13_16") (pintype "bidirectional"))
    )
    (net (code "78") (name "unconnected-(U3-IO14-Pad13)") (class "Default")
      (node (ref "U3") (pin "13") (pinfunction "IO14_13") (pintype "bidirectional"))
    )
    (net (code "79") (name "unconnected-(U3-IO15-Pad23)") (class "Default")
      (node (ref "U3") (pin "23") (pinfunction "IO15_23") (pintype "bidirectional"))
    )
    (net (code "80") (name "unconnected-(U3-IO18-Pad30)") (class "Default")
      (node (ref "U3") (pin "30") (pinfunction "IO18_30") (pintype "bidirectional"))
    )
    (net (code "81") (name "unconnected-(U3-IO19-Pad31)") (class "Default")
      (node (ref "U3") (pin "31") (pinfunction "IO19_31") (pintype "bidirectional"))
    )
    (net (code "82") (name "unconnected-(U3-IO23-Pad37)") (class "Default")
      (node (ref "U3") (pin "37") (pinfunction "IO23_37") (pintype "bidirectional"))
    )
    (net (code "83") (name "unconnected-(U3-IO27-Pad12)") (class "Default")
      (node (ref "U3") (pin "12") (pinfunction "IO27_12") (pintype "bidirectional"))
    )
    (net (code "84") (name "unconnected-(U3-IO32-Pad8)") (class "Default")
      (node (ref "U3") (pin "8") (pinfunction "IO32_8") (pintype "bidirectional"))
    )
    (net (code "85") (name "unconnected-(U3-IO33-Pad9)") (class "Default")
      (node (ref "U3") (pin "9") (pinfunction "IO33_9") (pintype "bidirectional"))
    )
    (net (code "86") (name "unconnected-(U3-IO34-Pad6)") (class "Default")
      (node (ref "U3") (pin "6") (pinfunction "IO34_6") (pintype "input"))
    )
    (net (code "87") (name "unconnected-(U3-IO35-Pad7)") (class "Default")
      (node (ref "U3") (pin "7") (pinfunction "IO35_7") (pintype "input"))
    )
    (net (code "88") (name "unconnected-(U3-SCK{slash}CLK-Pad20)") (class "Default")
      (node (ref "U3") (pin "20") (pinfunction "SCK/CLK_20") (pintype "bidirectional"))
    )
    (net (code "89") (name "unconnected-(U3-SCS{slash}CMD-Pad19)") (class "Default")
      (node (ref "U3") (pin "19") (pinfunction "SCS/CMD_19") (pintype "bidirectional"))
    )
    (net (code "90") (name "unconnected-(U3-SDI{slash}SD1-Pad22)") (class "Default")
      (node (ref "U3") (pin "22") (pinfunction "SDI/SD1_22") (pintype "bidirectional"))
    )
    (net (code "91") (name "unconnected-(U3-SDO{slash}SD0-Pad21)") (class "Default")
      (node (ref "U3") (pin "21") (pinfunction "SDO/SD0_21") (pintype "bidirectional"))
    )
    (net (code "92") (name "unconnected-(U3-SENSOR_VN-Pad5)") (class "Default")
      (node (ref "U3") (pin "5") (pinfunction "SENSOR_VN_5") (pintype "input"))
    )
    (net (code "93") (name "unconnected-(U3-SENSOR_VP-Pad4)") (class "Default")
      (node (ref "U3") (pin "4") (pinfunction "SENSOR_VP_4") (pintype "input"))
    )
    (net (code "94") (name "unconnected-(U3-SHD{slash}SD2-Pad17)") (class "Default")
      (node (ref "U3") (pin "17") (pinfunction "SHD/SD2_17") (pintype "bidirectional"))
    )
    (net (code "95") (name "unconnected-(U3-SWP{slash}SD3-Pad18)") (class "Default")
      (node (ref "U3") (pin "18") (pinfunction "SWP/SD3_18") (pintype "bidirectional"))
    )
  )
)
